# CONNECT.net
KiCad netlist of a schematic drawn in Altium Designer
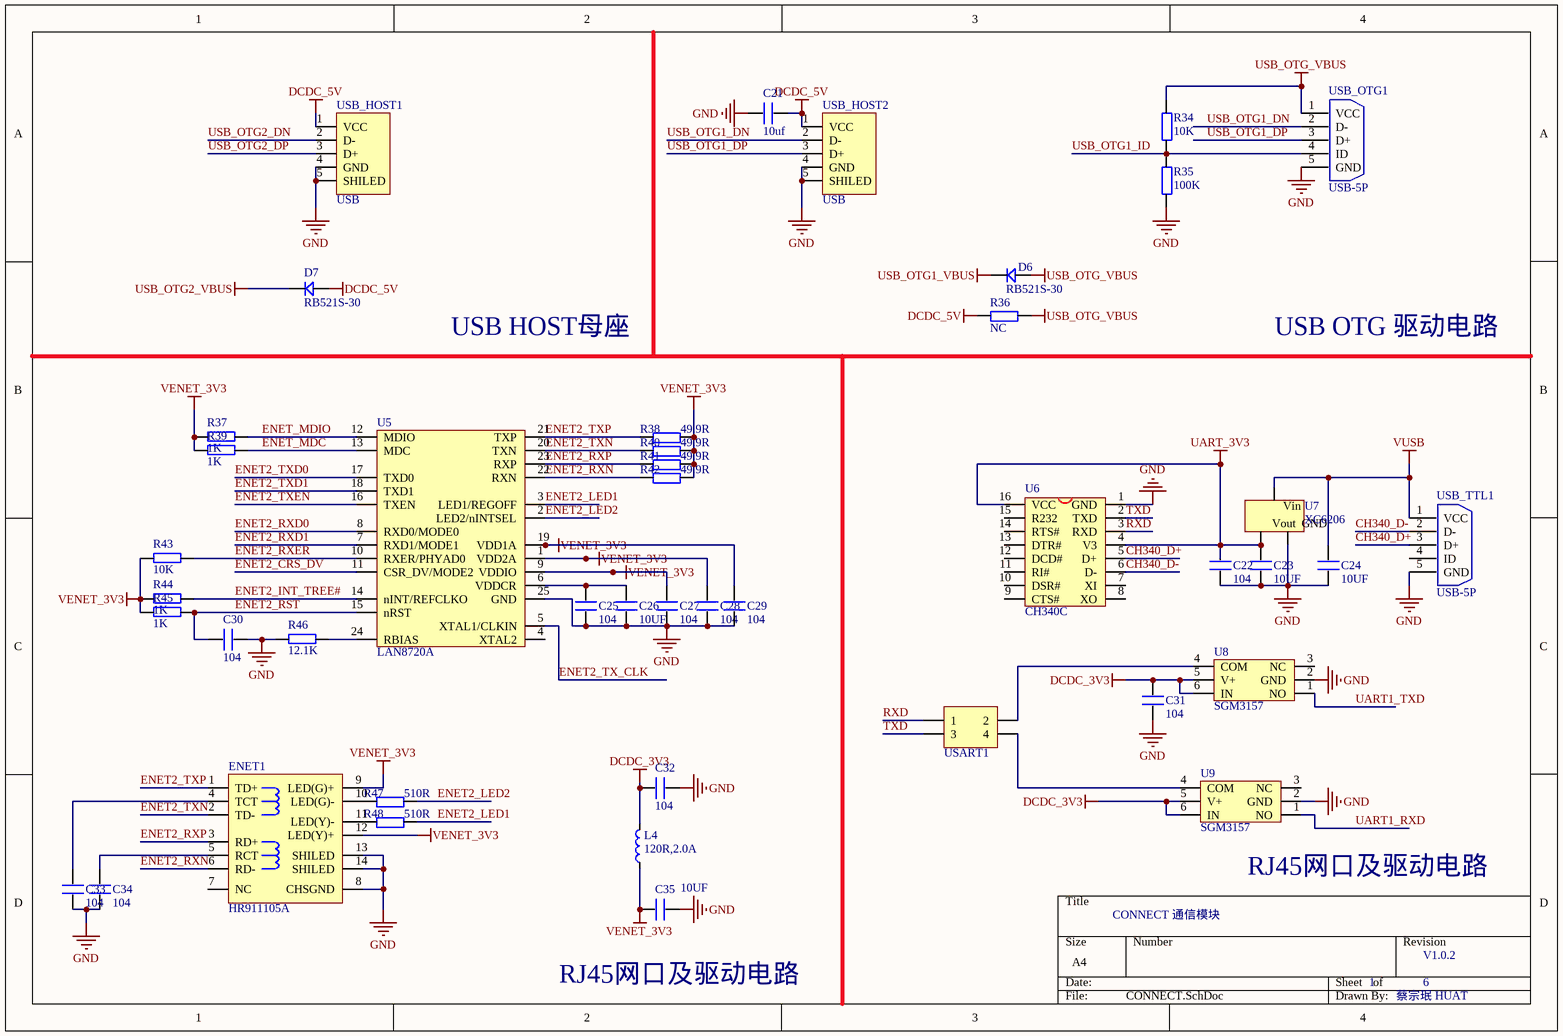
[diagram p0: CONNECT.SchDoc]

(export (version "E")
  (design (tool "Eeschema 10.0.6"))
  (components
    (comp (ref "C21") (value "10uf") (footprint "C_0603P") (libsource (lib "ZZW封装汇总") (part "C")))
    (comp (ref "C22") (value "104") (footprint "C_0603P") (libsource (lib "ZZW封装汇总") (part "C")))
    (comp (ref "C23") (value "10UF") (footprint "C_0603P") (libsource (lib "ZZW封装汇总") (part "C")))
    (comp (ref "C24") (value "10UF") (footprint "C_0603P") (libsource (lib "ZZW封装汇总") (part "C")))
    (comp (ref "C25") (value "104") (footprint "C_0603P") (libsource (lib "ZZW封装汇总") (part "C")))
    (comp (ref "C26") (value "10UF") (footprint "C_0603P") (libsource (lib "ZZW封装汇总") (part "C")))
    (comp (ref "C27") (value "104") (footprint "C_0603P") (libsource (lib "ZZW封装汇总") (part "C")))
    (comp (ref "C28") (value "104") (footprint "C_0603P") (libsource (lib "ZZW封装汇总") (part "C")))
    (comp (ref "C29") (value "104") (footprint "C_0603P") (libsource (lib "ZZW封装汇总") (part "C")))
    (comp (ref "C30") (value "104") (footprint "C_0603P") (libsource (lib "ZZW封装汇总") (part "C")))
    (comp (ref "C31") (value "104") (footprint "C_0603P") (libsource (lib "ZZW封装汇总") (part "C")))
    (comp (ref "C32") (value "104") (footprint "C_0603P") (libsource (lib "ZZW封装汇总") (part "C")))
    (comp (ref "C33") (value "104") (footprint "C_0603P") (libsource (lib "ZZW封装汇总") (part "C")))
    (comp (ref "C34") (value "104") (footprint "C_0603P") (libsource (lib "ZZW封装汇总") (part "C")))
    (comp (ref "C35") (value "10UF") (footprint "C_0603P") (libsource (lib "ZZW封装汇总") (part "C")))
    (comp (ref "D6")
      (value "RB521S-30")
      (footprint "DIODE 3*5.3")
      (description "1N4148")
      (libsource (lib "ZZW封装汇总") (part "D"))
    )
    (comp (ref "D7")
      (value "RB521S-30")
      (footprint "DIODE 3*5.3")
      (description "1N4148")
      (libsource (lib "ZZW封装汇总") (part "D"))
    )
    (comp (ref "ENET1")
      (value "HR911105A")
      (footprint "RJ-45A12")
      (description "带灯以太网接口")
      (fields (field (name "版权归属") "源创客"))
      (libsource (lib "IMX6UL_ALPHA(底板)_V2.0") (part "HR911105A"))
    )
    (comp (ref "L4")
      (value "120R,2.0A")
      (footprint "L 0603")
      (description "小功率贴片电感磁珠")
      (fields (field (name "版权归属") "源创客"))
      (libsource (lib "IMX6UL_ALPHA(底板)_V2.0") (part "L"))
    )
    (comp (ref "R34") (value "10K") (footprint "R_0603P") (libsource (lib "ZZW封装汇总") (part "R")))
    (comp (ref "R35") (value "100K") (footprint "R_0603P") (libsource (lib "ZZW封装汇总") (part "R")))
    (comp (ref "R36") (value "NC") (footprint "R_0603P") (libsource (lib "ZZW封装汇总") (part "R")))
    (comp (ref "R37") (value "1K") (footprint "R_0603P") (libsource (lib "ZZW封装汇总") (part "R")))
    (comp (ref "R38") (value "49.9R") (footprint "R_0603P") (libsource (lib "ZZW封装汇总") (part "R")))
    (comp (ref "R39") (value "1K") (footprint "R_0603P") (libsource (lib "ZZW封装汇总") (part "R")))
    (comp (ref "R40") (value "49.9R") (footprint "R_0603P") (libsource (lib "ZZW封装汇总") (part "R")))
    (comp (ref "R41") (value "49.9R") (footprint "R_0603P") (libsource (lib "ZZW封装汇总") (part "R")))
    (comp (ref "R42") (value "49.9R") (footprint "R_0603P") (libsource (lib "ZZW封装汇总") (part "R")))
    (comp (ref "R43") (value "10K") (footprint "R_0603P") (libsource (lib "ZZW封装汇总") (part "R")))
    (comp (ref "R44") (value "1K") (footprint "R_0603P") (libsource (lib "ZZW封装汇总") (part "R")))
    (comp (ref "R45") (value "1K") (footprint "R_0603P") (libsource (lib "ZZW封装汇总") (part "R")))
    (comp (ref "R46") (value "12.1K") (footprint "R_0603P") (libsource (lib "ZZW封装汇总") (part "R")))
    (comp (ref "R47") (value "510R") (footprint "R_0603P") (libsource (lib "ZZW封装汇总") (part "R")))
    (comp (ref "R48") (value "510R") (footprint "R_0603P") (libsource (lib "ZZW封装汇总") (part "R")))
    (comp (ref "U5")
      (value "LAN8720A")
      (footprint "QFN24")
      (description "ETH PHY")
      (libsource (lib "IMX6UL_ALPHA(底板)_V2.0") (part "LAN8720"))
    )
    (comp (ref "U6")
      (value "CH340C")
      (footprint "SOP16_N")
      (description "USB2UART")
      (libsource (lib "IMX6UL_ALPHA(底板)_V2.0") (part "CH340G"))
    )
    (comp (ref "U7")
      (value "XC6206")
      (footprint "SOT23-3N")
      (description "LDO")
      (libsource (lib "IMX6UL_ALPHA(底板)_V2.0") (part "LDO XC6206"))
    )
    (comp (ref "U8")
      (value "SGM3157")
      (footprint "SOT363-6L")
      (description "单路双掷模拟开关")
      (libsource (lib "IMX6UL_ALPHA(底板)_V2.0") (part "SGM3157"))
    )
    (comp (ref "U9")
      (value "SGM3157")
      (footprint "SOT363-6L")
      (description "单路双掷模拟开关")
      (libsource (lib "IMX6UL_ALPHA(底板)_V2.0") (part "SGM3157"))
    )
    (comp (ref "USART1")
      (value "Header2X2")
      (footprint "HDR-2X2")
      (description "2*2P接插件")
      (fields (field (name "版权归属") "源创客"))
      (libsource (lib "IMX6UL_ALPHA(底板)_V2.0") (part "Header 2X2"))
    )
    (comp (ref "USB_HOST1")
      (value "USB")
      (footprint "USB-A/S_E")
      (description "USB-A型母接口")
      (fields (field (name "版权归属") "源创客"))
      (libsource (lib "IMX6UL_ALPHA(底板)_V2.0") (part "USB-A/S"))
    )
    (comp (ref "USB_HOST2")
      (value "USB")
      (footprint "USB-A/S_E")
      (description "USB-A型母接口")
      (fields (field (name "版权归属") "源创客"))
      (libsource (lib "IMX6UL_ALPHA(底板)_V2.0") (part "USB-A/S"))
    )
    (comp (ref "USB_OTG1")
      (value "USB-5P")
      (footprint "USB-MINI-A")
      (description "微型USB母座")
      (fields (field (name "版权归属") "源创客"))
      (libsource (lib "IMX6UL_ALPHA(底板)_V2.0") (part "USB-5P"))
    )
    (comp (ref "USB_TTL1")
      (value "USB-5P")
      (footprint "USB-MINI-A")
      (description "微型USB母座")
      (fields (field (name "版权归属") "源创客"))
      (libsource (lib "IMX6UL_ALPHA(底板)_V2.0") (part "USB-5P"))
    )
  )
  (nets
    (net (code "1") (name "/CH340_D+") (class "Default")
      (node (ref "U6") (pin "5") (pinfunction "D+_5") (pintype "passive"))
      (node (ref "USB_TTL1") (pin "3") (pinfunction "D+_3") (pintype "passive"))
    )
    (net (code "2") (name "/CH340_D-") (class "Default")
      (node (ref "U6") (pin "6") (pinfunction "D-_6") (pintype "passive"))
      (node (ref "USB_TTL1") (pin "2") (pinfunction "D-_2") (pintype "passive"))
    )
    (net (code "3") (name "/ENET2_CRS_DV") (class "Default")
      (node (ref "U5") (pin "11") (pinfunction "CSR_DV/MODE2_11") (pintype "passive"))
    )
    (net (code "4") (name "/ENET2_INT_TREE#") (class "Default")
      (node (ref "R44") (pin "1") (pintype "passive"))
      (node (ref "U5") (pin "14") (pinfunction "nINT/REFCLKO_14") (pintype "passive"))
    )
    (net (code "5") (name "/ENET2_LED1") (class "Default")
      (node (ref "R48") (pin "2") (pintype "passive"))
      (node (ref "U5") (pin "3") (pinfunction "LED1/REGOFF_3") (pintype "passive"))
    )
    (net (code "6") (name "/ENET2_LED2") (class "Default")
      (node (ref "R47") (pin "2") (pintype "passive"))
      (node (ref "U5") (pin "2") (pinfunction "LED2/nINTSEL_2") (pintype "passive"))
    )
    (net (code "7") (name "/ENET2_RST") (class "Default")
      (node (ref "C30") (pin "2") (pintype "passive"))
      (node (ref "R45") (pin "1") (pintype "passive"))
      (node (ref "U5") (pin "15") (pinfunction "nRST_15") (pintype "passive"))
    )
    (net (code "8") (name "/ENET2_RXD0") (class "Default")
      (node (ref "U5") (pin "8") (pinfunction "RXD0/MODE0_8") (pintype "passive"))
    )
    (net (code "9") (name "/ENET2_RXD1") (class "Default")
      (node (ref "U5") (pin "7") (pinfunction "RXD1/MODE1_7") (pintype "passive"))
    )
    (net (code "10") (name "/ENET2_RXER") (class "Default")
      (node (ref "R43") (pin "1") (pintype "passive"))
      (node (ref "U5") (pin "10") (pinfunction "RXER/PHYAD0_10") (pintype "passive"))
    )
    (net (code "11") (name "/ENET2_RXN") (class "Default")
      (node (ref "ENET1") (pin "6") (pinfunction "RD-_6") (pintype "passive"))
      (node (ref "R42") (pin "1") (pintype "passive"))
      (node (ref "U5") (pin "22") (pinfunction "RXN_22") (pintype "passive"))
    )
    (net (code "12") (name "/ENET2_RXP") (class "Default")
      (node (ref "ENET1") (pin "3") (pinfunction "RD+_3") (pintype "passive"))
      (node (ref "R41") (pin "1") (pintype "passive"))
      (node (ref "U5") (pin "23") (pinfunction "RXP_23") (pintype "passive"))
    )
    (net (code "13") (name "/ENET2_TXD0") (class "Default")
      (node (ref "U5") (pin "17") (pinfunction "TXD0_17") (pintype "passive"))
    )
    (net (code "14") (name "/ENET2_TXD1") (class "Default")
      (node (ref "U5") (pin "18") (pinfunction "TXD1_18") (pintype "passive"))
    )
    (net (code "15") (name "/ENET2_TXEN") (class "Default")
      (node (ref "U5") (pin "16") (pinfunction "TXEN_16") (pintype "passive"))
    )
    (net (code "16") (name "/ENET2_TXN") (class "Default")
      (node (ref "ENET1") (pin "2") (pinfunction "TD-_2") (pintype "passive"))
      (node (ref "R40") (pin "1") (pintype "passive"))
      (node (ref "U5") (pin "20") (pinfunction "TXN_20") (pintype "passive"))
    )
    (net (code "17") (name "/ENET2_TXP") (class "Default")
      (node (ref "ENET1") (pin "1") (pinfunction "TD+_1") (pintype "passive"))
      (node (ref "R38") (pin "1") (pintype "passive"))
      (node (ref "U5") (pin "21") (pinfunction "TXP_21") (pintype "passive"))
    )
    (net (code "18") (name "/ENET2_TX_CLK") (class "Default")
      (node (ref "U5") (pin "5") (pinfunction "XTAL1/CLKIN_5") (pintype "passive"))
    )
    (net (code "19") (name "/ENET_MDC") (class "Default")
      (node (ref "R39") (pin "1") (pintype "passive"))
      (node (ref "U5") (pin "13") (pinfunction "MDC_13") (pintype "passive"))
    )
    (net (code "20") (name "/ENET_MDIO") (class "Default")
      (node (ref "R37") (pin "1") (pintype "passive"))
      (node (ref "U5") (pin "12") (pinfunction "MDIO_12") (pintype "passive"))
    )
    (net (code "21") (name "/RXD") (class "Default")
      (node (ref "U6") (pin "3") (pinfunction "RXD_3") (pintype "passive"))
      (node (ref "USART1") (pin "1") (pinfunction "1_1") (pintype "passive"))
    )
    (net (code "22") (name "/TXD") (class "Default")
      (node (ref "U6") (pin "2") (pinfunction "TXD_2") (pintype "passive"))
      (node (ref "USART1") (pin "3") (pinfunction "3_3") (pintype "passive"))
    )
    (net (code "23") (name "/UART1_RXD") (class "Default")
      (node (ref "U9") (pin "1") (pinfunction "NO_1") (pintype "passive"))
    )
    (net (code "24") (name "/UART1_TXD") (class "Default")
      (node (ref "U8") (pin "1") (pinfunction "NO_1") (pintype "passive"))
    )
    (net (code "25") (name "/USB_OTG1_DN") (class "Default")
      (node (ref "USB_HOST2") (pin "2") (pinfunction "D-_2") (pintype "passive"))
      (node (ref "USB_OTG1") (pin "2") (pinfunction "D-_2") (pintype "passive"))
    )
    (net (code "26") (name "/USB_OTG1_DP") (class "Default")
      (node (ref "USB_HOST2") (pin "3") (pinfunction "D+_3") (pintype "passive"))
      (node (ref "USB_OTG1") (pin "3") (pinfunction "D+_3") (pintype "passive"))
    )
    (net (code "27") (name "/USB_OTG1_ID") (class "Default")
      (node (ref "R34") (pin "1") (pintype "passive"))
      (node (ref "R35") (pin "2") (pintype "passive"))
      (node (ref "USB_OTG1") (pin "4") (pinfunction "ID_4") (pintype "passive"))
    )
    (net (code "28") (name "/USB_OTG2_DN") (class "Default")
      (node (ref "USB_HOST1") (pin "2") (pinfunction "D-_2") (pintype "passive"))
    )
    (net (code "29") (name "/USB_OTG2_DP") (class "Default")
      (node (ref "USB_HOST1") (pin "3") (pinfunction "D+_3") (pintype "passive"))
    )
    (net (code "30") (name "DCDC_3V3") (class "Default")
      (node (ref "C31") (pin "2") (pintype "passive"))
      (node (ref "C32") (pin "2") (pintype "passive"))
      (node (ref "L4") (pin "2") (pinfunction "2_2") (pintype "passive"))
      (node (ref "U8") (pin "5") (pinfunction "V+_5") (pintype "passive"))
      (node (ref "U8") (pin "6") (pinfunction "IN_6") (pintype "passive"))
      (node (ref "U9") (pin "5") (pinfunction "V+_5") (pintype "passive"))
      (node (ref "U9") (pin "6") (pinfunction "IN_6") (pintype "passive"))
    )
    (net (code "31") (name "DCDC_5V") (class "Default")
      (node (ref "C21") (pin "2") (pintype "passive"))
      (node (ref "D7") (pin "1") (pintype "passive"))
      (node (ref "R36") (pin "1") (pintype "passive"))
      (node (ref "USB_HOST1") (pin "1") (pinfunction "VCC_1") (pintype "passive"))
      (node (ref "USB_HOST2") (pin "1") (pinfunction "VCC_1") (pintype "passive"))
    )
    (net (code "32") (name "GND") (class "Default")
      (node (ref "C21") (pin "1") (pintype "passive"))
      (node (ref "C22") (pin "1") (pintype "passive"))
      (node (ref "C23") (pin "1") (pintype "passive"))
      (node (ref "C24") (pin "1") (pintype "passive"))
      (node (ref "C25") (pin "1") (pintype "passive"))
      (node (ref "C26") (pin "1") (pintype "passive"))
      (node (ref "C27") (pin "1") (pintype "passive"))
      (node (ref "C28") (pin "1") (pintype "passive"))
      (node (ref "C29") (pin "1") (pintype "passive"))
      (node (ref "C30") (pin "1") (pintype "passive"))
      (node (ref "C31") (pin "1") (pintype "passive"))
      (node (ref "C32") (pin "1") (pintype "passive"))
      (node (ref "C33") (pin "1") (pintype "passive"))
      (node (ref "C34") (pin "1") (pintype "passive"))
      (node (ref "C35") (pin "1") (pintype "passive"))
      (node (ref "ENET1") (pin "13") (pinfunction "SHILED_13") (pintype "passive"))
      (node (ref "ENET1") (pin "14") (pinfunction "SHILED_14") (pintype "passive"))
      (node (ref "ENET1") (pin "8") (pinfunction "CHSGND_8") (pintype "passive"))
      (node (ref "R35") (pin "1") (pintype "passive"))
      (node (ref "R46") (pin "2") (pintype "passive"))
      (node (ref "U5") (pin "25") (pinfunction "GND_25") (pintype "passive"))
      (node (ref "U6") (pin "1") (pinfunction "GND_1") (pintype "passive"))
      (node (ref "U7") (pin "1") (pinfunction "GND_1") (pintype "passive"))
      (node (ref "U8") (pin "2") (pinfunction "GND_2") (pintype "passive"))
      (node (ref "U9") (pin "2") (pinfunction "GND_2") (pintype "passive"))
      (node (ref "USB_HOST1") (pin "4") (pinfunction "GND_4") (pintype "passive"))
      (node (ref "USB_HOST1") (pin "5") (pinfunction "SHILED_5") (pintype "passive"))
      (node (ref "USB_HOST2") (pin "4") (pinfunction "GND_4") (pintype "passive"))
      (node (ref "USB_HOST2") (pin "5") (pinfunction "SHILED_5") (pintype "passive"))
      (node (ref "USB_OTG1") (pin "5") (pinfunction "GND_5") (pintype "passive"))
      (node (ref "USB_TTL1") (pin "5") (pinfunction "GND_5") (pintype "passive"))
    )
    (net (code "33") (name "Net-(ENET1-LED(G)-)") (class "Default")
      (node (ref "ENET1") (pin "10") (pinfunction "LED(G)-_10") (pintype "passive"))
      (node (ref "R47") (pin "1") (pintype "passive"))
    )
    (net (code "34") (name "Net-(ENET1-LED(Y)-)") (class "Default")
      (node (ref "ENET1") (pin "11") (pinfunction "LED(Y)-_11") (pintype "passive"))
      (node (ref "R48") (pin "1") (pintype "passive"))
    )
    (net (code "35") (name "Net-(ENET1-RCT)") (class "Default")
      (node (ref "C34") (pin "2") (pintype "passive"))
      (node (ref "ENET1") (pin "5") (pinfunction "RCT_5") (pintype "passive"))
    )
    (net (code "36") (name "Net-(ENET1-TCT)") (class "Default")
      (node (ref "C33") (pin "2") (pintype "passive"))
      (node (ref "ENET1") (pin "4") (pinfunction "TCT_4") (pintype "passive"))
    )
    (net (code "37") (name "Net-(U5-RBIAS)") (class "Default")
      (node (ref "R46") (pin "1") (pintype "passive"))
      (node (ref "U5") (pin "24") (pinfunction "RBIAS_24") (pintype "passive"))
    )
    (net (code "38") (name "Net-(U5-VDDCR)") (class "Default")
      (node (ref "C25") (pin "2") (pintype "passive"))
      (node (ref "C26") (pin "2") (pintype "passive"))
      (node (ref "U5") (pin "6") (pinfunction "VDDCR_6") (pintype "passive"))
    )
    (net (code "39") (name "Net-(U8-COM)") (class "Default")
      (node (ref "U8") (pin "4") (pinfunction "COM_4") (pintype "passive"))
      (node (ref "USART1") (pin "2") (pinfunction "2_2") (pintype "passive"))
    )
    (net (code "40") (name "Net-(U9-COM)") (class "Default")
      (node (ref "U9") (pin "4") (pinfunction "COM_4") (pintype "passive"))
      (node (ref "USART1") (pin "4") (pinfunction "4_4") (pintype "passive"))
    )
    (net (code "41") (name "UART_3V3") (class "Default")
      (node (ref "C22") (pin "2") (pintype "passive"))
      (node (ref "C23") (pin "2") (pintype "passive"))
      (node (ref "U6") (pin "16") (pinfunction "VCC_16") (pintype "passive"))
      (node (ref "U6") (pin "4") (pinfunction "V3_4") (pintype "passive"))
      (node (ref "U7") (pin "2") (pinfunction "Vout_2") (pintype "passive"))
    )
    (net (code "42") (name "USB_OTG1_VBUS") (class "Default") (node (ref "D6") (pin "2") (pintype "passive")))
    (net (code "43") (name "USB_OTG2_VBUS") (class "Default") (node (ref "D7") (pin "2") (pintype "passive")))
    (net (code "44") (name "USB_OTG_VBUS") (class "Default")
      (node (ref "D6") (pin "1") (pintype "passive"))
      (node (ref "R34") (pin "2") (pintype "passive"))
      (node (ref "R36") (pin "2") (pintype "passive"))
      (node (ref "USB_OTG1") (pin "1") (pinfunction "VCC_1") (pintype "passive"))
    )
    (net (code "45") (name "VENET_3V3") (class "Default")
      (node (ref "C27") (pin "2") (pintype "passive"))
      (node (ref "C28") (pin "2") (pintype "passive"))
      (node (ref "C29") (pin "2") (pintype "passive"))
      (node (ref "C35") (pin "2") (pintype "passive"))
      (node (ref "ENET1") (pin "12") (pinfunction "LED(Y)+_12") (pintype "passive"))
      (node (ref "ENET1") (pin "9") (pinfunction "LED(G)+_9") (pintype "passive"))
      (node (ref "L4") (pin "1") (pinfunction "1_1") (pintype "passive"))
      (node (ref "R37") (pin "2") (pintype "passive"))
      (node (ref "R38") (pin "2") (pintype "passive"))
      (node (ref "R39") (pin "2") (pintype "passive"))
      (node (ref "R40") (pin "2") (pintype "passive"))
      (node (ref "R41") (pin "2") (pintype "passive"))
      (node (ref "R42") (pin "2") (pintype "passive"))
      (node (ref "R43") (pin "2") (pintype "passive"))
      (node (ref "R44") (pin "2") (pintype "passive"))
      (node (ref "R45") (pin "2") (pintype "passive"))
      (node (ref "U5") (pin "1") (pinfunction "VDD2A_1") (pintype "passive"))
      (node (ref "U5") (pin "19") (pinfunction "VDD1A_19") (pintype "passive"))
      (node (ref "U5") (pin "9") (pinfunction "VDDIO_9") (pintype "passive"))
    )
    (net (code "46") (name "VUSB") (class "Default")
      (node (ref "C24") (pin "2") (pintype "passive"))
      (node (ref "U7") (pin "3") (pinfunction "Vin_3") (pintype "passive"))
      (node (ref "USB_TTL1") (pin "1") (pinfunction "VCC_1") (pintype "passive"))
    )
    (net (code "47") (name "unconnected-(ENET1-NC-Pad7)") (class "Default")
      (node (ref "ENET1") (pin "7") (pinfunction "NC_7") (pintype "passive"))
    )
    (net (code "48") (name "unconnected-(U5-XTAL2-Pad4)") (class "Default")
      (node (ref "U5") (pin "4") (pinfunction "XTAL2_4") (pintype "passive"))
    )
    (net (code "49") (name "unconnected-(U6-CTS#-Pad9)") (class "Default")
      (node (ref "U6") (pin "9") (pinfunction "CTS#_9") (pintype "passive"))
    )
    (net (code "50") (name "unconnected-(U6-DCD#-Pad12)") (class "Default")
      (node (ref "U6") (pin "12") (pinfunction "DCD#_12") (pintype "passive"))
    )
    (net (code "51") (name "unconnected-(U6-DSR#-Pad10)") (class "Default")
      (node (ref "U6") (pin "10") (pinfunction "DSR#_10") (pintype "passive"))
    )
    (net (code "52") (name "unconnected-(U6-DTR#-Pad13)") (class "Default")
      (node (ref "U6") (pin "13") (pinfunction "DTR#_13") (pintype "passive"))
    )
    (net (code "53") (name "unconnected-(U6-R232-Pad15)") (class "Default")
      (node (ref "U6") (pin "15") (pinfunction "R232_15") (pintype "passive"))
    )
    (net (code "54") (name "unconnected-(U6-RI#-Pad11)") (class "Default")
      (node (ref "U6") (pin "11") (pinfunction "RI#_11") (pintype "passive"))
    )
    (net (code "55") (name "unconnected-(U6-RTS#-Pad14)") (class "Default")
      (node (ref "U6") (pin "14") (pinfunction "RTS#_14") (pintype "passive"))
    )
    (net (code "56") (name "unconnected-(U6-XI-Pad7)") (class "Default")
      (node (ref "U6") (pin "7") (pinfunction "XI_7") (pintype "passive"))
    )
    (net (code "57") (name "unconnected-(U6-XO-Pad8)") (class "Default")
      (node (ref "U6") (pin "8") (pinfunction "XO_8") (pintype "passive"))
    )
    (net (code "58") (name "unconnected-(U8-NC-Pad3)") (class "Default")
      (node (ref "U8") (pin "3") (pinfunction "NC_3") (pintype "passive"))
    )
    (net (code "59") (name "unconnected-(U9-NC-Pad3)") (class "Default")
      (node (ref "U9") (pin "3") (pinfunction "NC_3") (pintype "passive"))
    )
    (net (code "60") (name "unconnected-(USB_TTL1-ID-Pad4)") (class "Default")
      (node (ref "USB_TTL1") (pin "4") (pinfunction "ID_4") (pintype "passive"))
    )
  )
)
